# 08_-_Resolver.net
KiCad netlist of a schematic drawn in Altium Designer
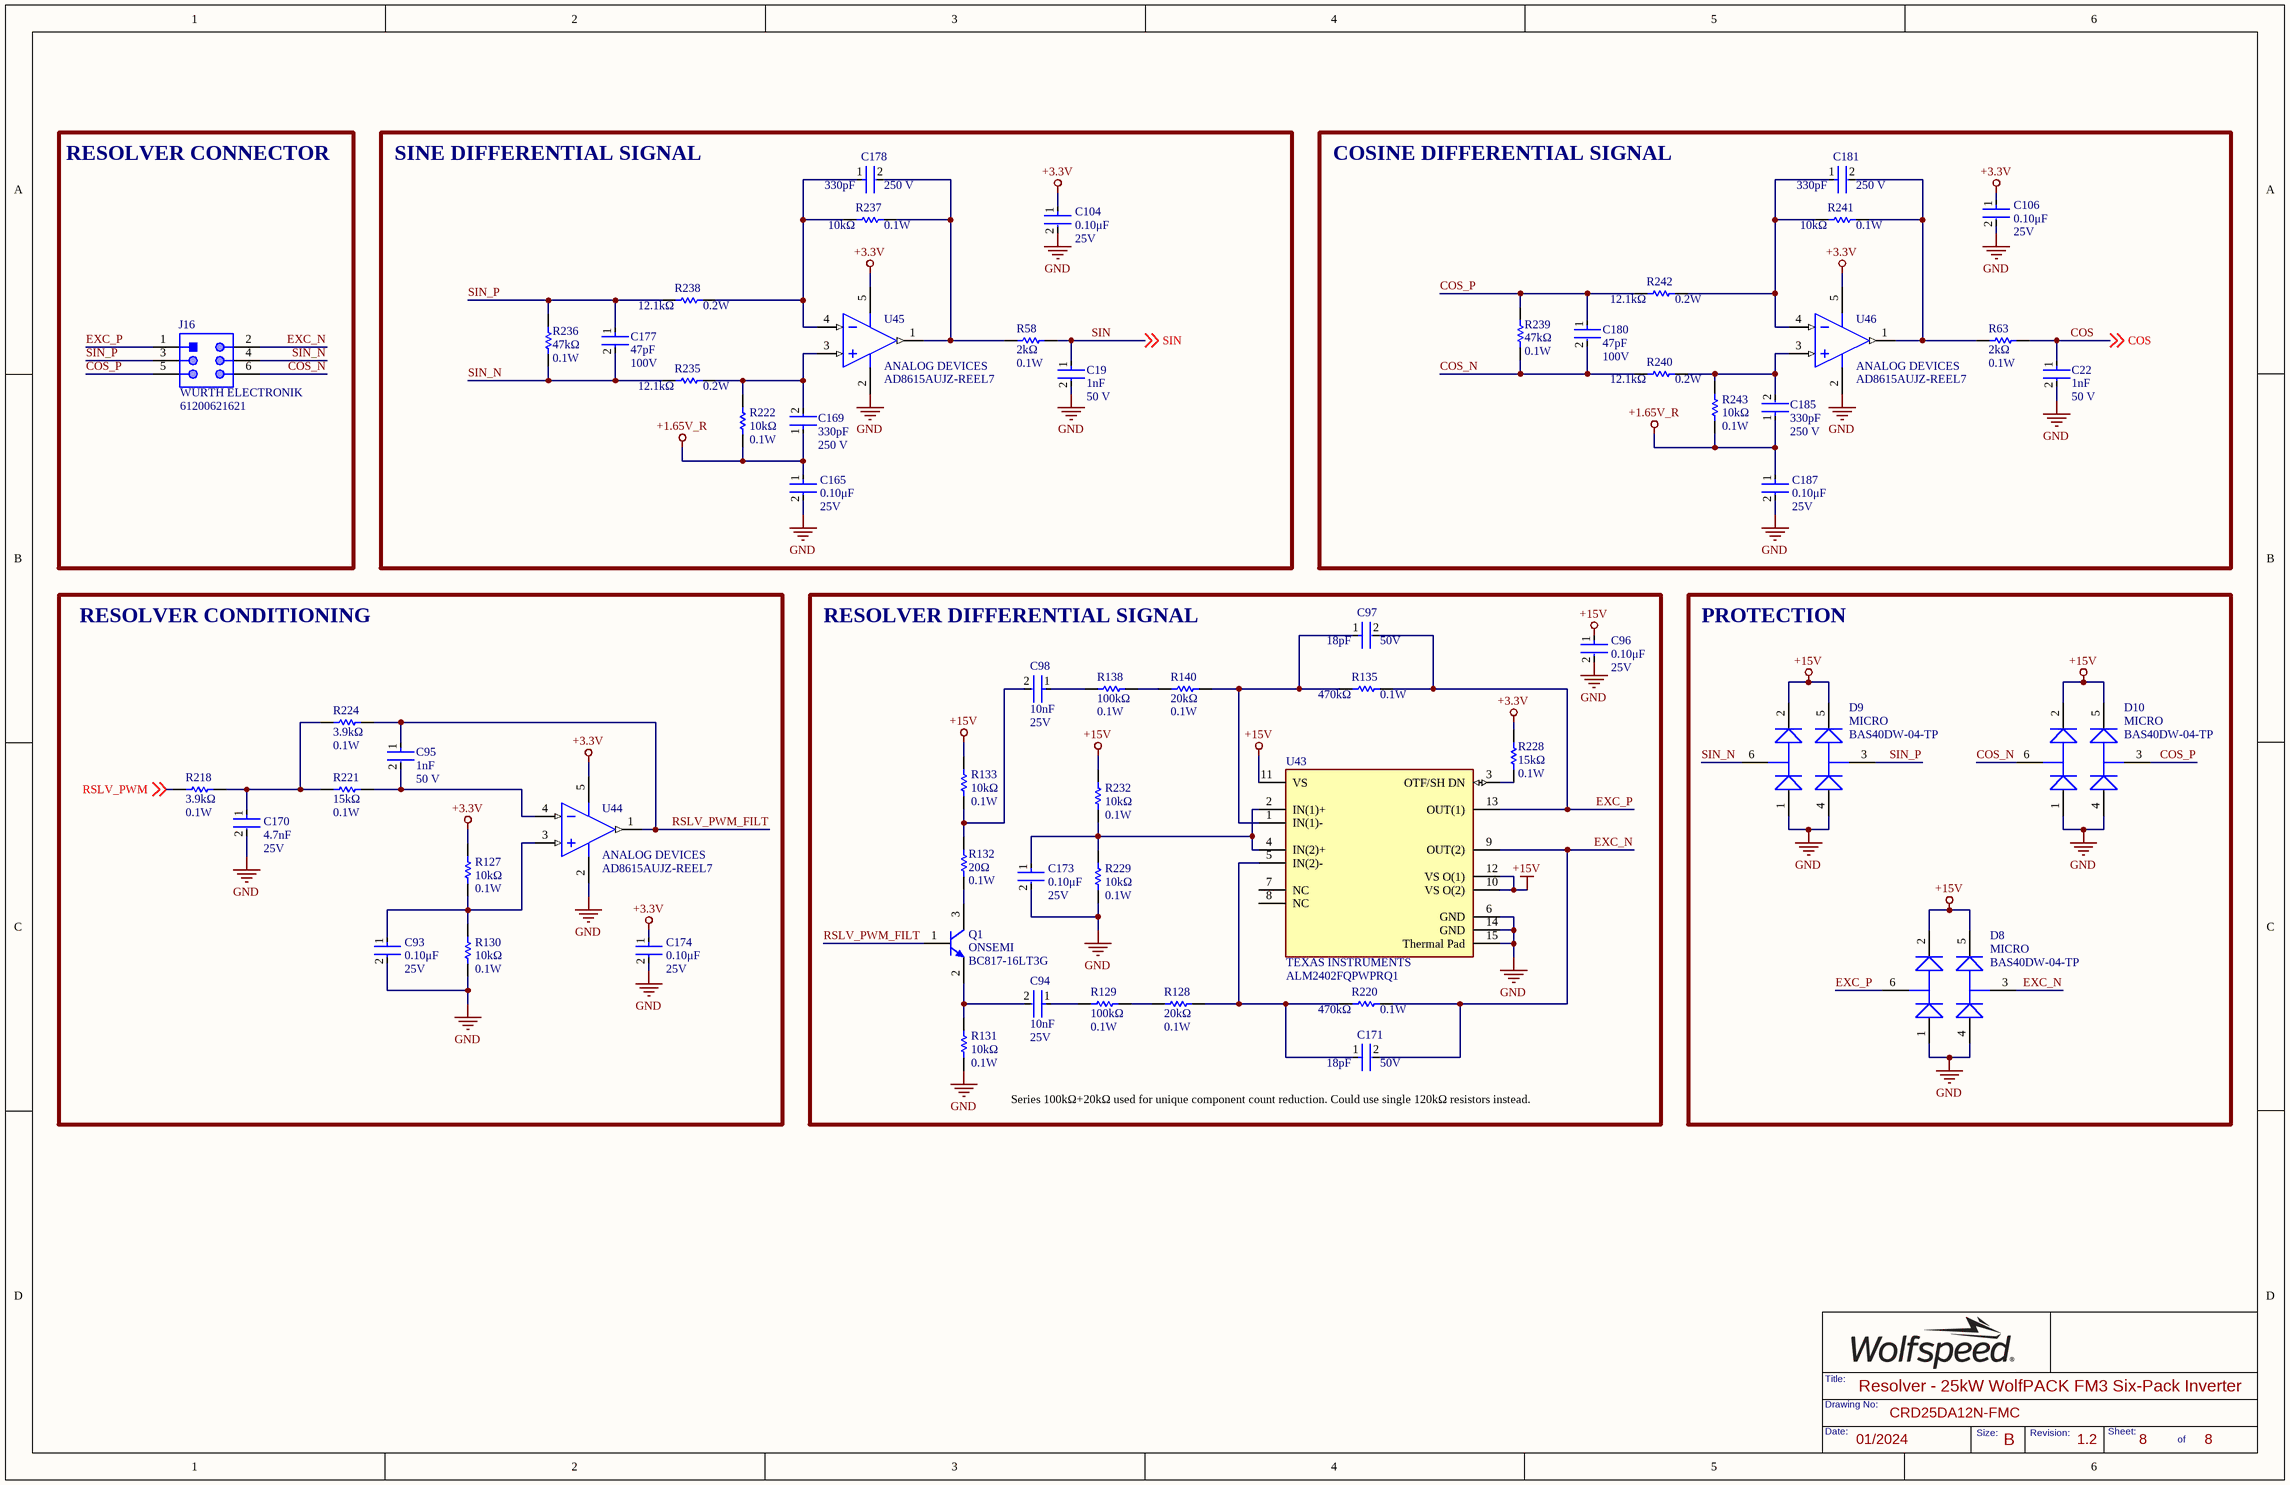
[diagram p0: 08 - Resolver.SchDoc]

(export (version "E")
  (design (tool "Eeschema 10.0.6"))
  (components
    (comp (ref "C19")
      (value "C0603C102K5RACAUTO")
      (footprint "FP-C0603C-CF-IPC_B")
      (description "CAP CER 1000PF 50V X7R 0603")
      (fields
        (field (name "CAPACITANCE") "1nF")
        (field (name "TOLERANCE") "0.1")
        (field (name "VOLTAGE RATING") "50 V")
        (field (name "OCTOPART") "https://octopart.com/c0603c102k5racauto-kemet-18822673")
      )
      (libsource (lib "Altium Content Vault") (part "b4654b650e69147ec39a6b967a45e02"))
    )
    (comp (ref "C22")
      (value "C0603C102K5RACAUTO")
      (footprint "FP-C0603C-CF-IPC_B")
      (description "CAP CER 1000PF 50V X7R 0603")
      (fields
        (field (name "CAPACITANCE") "1nF")
        (field (name "TOLERANCE") "0.1")
        (field (name "VOLTAGE RATING") "50 V")
        (field (name "OCTOPART") "https://octopart.com/c0603c102k5racauto-kemet-18822673")
      )
      (libsource (lib "Altium Content Vault") (part "b4654b650e69147ec39a6b967a45e02"))
    )
    (comp (ref "C93")
      (value "C0603C104K3RACTU")
      (footprint "FP-C0603C-CF-IPC_B")
      (description "CAP CER 0.1UF 25V X7R 0603")
      (fields
        (field (name "VOLTAGE RATING") "25V")
        (field (name "OCTOPART") "https://octopart.com/c0603c104k3ractu-kemet-127541")
        (field (name "MANUFACTURER") "KEMET")
        (field (name "CAPACITANCE") "0.10μF")
      )
      (libsource (lib "Altium Content Vault") (part "b4654b650e69147ec39a6b967a45e02"))
    )
    (comp (ref "C94")
      (value "10nF")
      (footprint "FP-C0603C-CF-IPC_B")
      (description "CAP CER 10000PF 25V X7R 0603")
      (fields
        (field (name "MANUFACTURER") "SAMSUNG")
        (field (name "MANUFACTURER PART NUMBER") "CL10B103KA8WPNC")
        (field (name "VOLTAGE RATING") "25V")
      )
      (libsource (lib "Inverter_25kW") (part "CL10B103KA8WPNC"))
    )
    (comp (ref "C95")
      (value "C0603C102K5RACAUTO")
      (footprint "FP-C0603C-CF-IPC_B")
      (description "CAP CER 1000PF 50V X7R 0603")
      (fields
        (field (name "CAPACITANCE") "1nF")
        (field (name "TOLERANCE") "0.1")
        (field (name "VOLTAGE RATING") "50 V")
        (field (name "OCTOPART") "https://octopart.com/c0603c102k5racauto-kemet-18822673")
      )
      (libsource (lib "Altium Content Vault") (part "b4654b650e69147ec39a6b967a45e02"))
    )
    (comp (ref "C96")
      (value "C0603C104K3RACTU")
      (footprint "FP-C0603C-CF-IPC_B")
      (description "CAP CER 0.1UF 25V X7R 0603")
      (fields
        (field (name "VOLTAGE RATING") "25V")
        (field (name "OCTOPART") "https://octopart.com/c0603c104k3ractu-kemet-127541")
        (field (name "MANUFACTURER") "KEMET")
        (field (name "CAPACITANCE") "0.10μF")
      )
      (libsource (lib "Altium Content Vault") (part "b4654b650e69147ec39a6b967a45e02"))
    )
    (comp (ref "C97")
      (value "06035A180JAT2A")
      (footprint "FP-C0603C-CF-IPC_B")
      (description "CAP CER 18PF 50V C0G/NP0 0603")
      (fields
        (field (name "MANUFACTURER") "KYOCERA AVX")
        (field (name "TOLERANCE") "5%")
        (field (name "CAPACITANCE") "18pF")
        (field (name "VOLTAGE RATING") "50V")
      )
      (libsource (lib "Inverter_25kW") (part "06035A180JAT2A"))
    )
    (comp (ref "C98")
      (value "10nF")
      (footprint "FP-C0603C-CF-IPC_B")
      (description "CAP CER 10000PF 25V X7R 0603")
      (fields
        (field (name "MANUFACTURER") "SAMSUNG")
        (field (name "MANUFACTURER PART NUMBER") "CL10B103KA8WPNC")
        (field (name "VOLTAGE RATING") "25V")
      )
      (libsource (lib "Inverter_25kW") (part "CL10B103KA8WPNC"))
    )
    (comp (ref "C104")
      (value "C0603C104K3RACTU")
      (footprint "FP-C0603C-CF-IPC_B")
      (description "CAP CER 0.1UF 25V X7R 0603")
      (fields
        (field (name "VOLTAGE RATING") "25V")
        (field (name "OCTOPART") "https://octopart.com/c0603c104k3ractu-kemet-127541")
        (field (name "MANUFACTURER") "KEMET")
        (field (name "CAPACITANCE") "0.10μF")
      )
      (libsource (lib "Altium Content Vault") (part "b4654b650e69147ec39a6b967a45e02"))
    )
    (comp (ref "C106")
      (value "C0603C104K3RACTU")
      (footprint "FP-C0603C-CF-IPC_B")
      (description "CAP CER 0.1UF 25V X7R 0603")
      (fields
        (field (name "VOLTAGE RATING") "25V")
        (field (name "OCTOPART") "https://octopart.com/c0603c104k3ractu-kemet-127541")
        (field (name "MANUFACTURER") "KEMET")
        (field (name "CAPACITANCE") "0.10μF")
      )
      (libsource (lib "Altium Content Vault") (part "b4654b650e69147ec39a6b967a45e02"))
    )
    (comp (ref "C165")
      (value "C0603C104K3RACTU")
      (footprint "FP-C0603C-CF-IPC_B")
      (description "CAP CER 0.1UF 25V X7R 0603")
      (fields
        (field (name "VOLTAGE RATING") "25V")
        (field (name "OCTOPART") "https://octopart.com/c0603c104k3ractu-kemet-127541")
        (field (name "MANUFACTURER") "KEMET")
        (field (name "CAPACITANCE") "0.10μF")
      )
      (libsource (lib "Altium Content Vault") (part "b4654b650e69147ec39a6b967a45e02"))
    )
    (comp (ref "C169")
      (value "330pF")
      (footprint "FP-C0603C-CF-IPC_B")
      (description "CAP CER 330PF 250V C0G/NP0 0603")
      (fields
        (field (name "OCTOPART") "https://octopart.com/c0603c331jagac7867-kemet-83501965")
        (field (name "MANUFACTURER PART NUMBER") "C0603C331JAGAC7867")
        (field (name "VOLTAGE RATING") "250 V")
      )
      (libsource (lib "Altium Content Vault") (part "b4654b650e69147ec39a6b967a45e02"))
    )
    (comp (ref "C170")
      (value "C0603C472K3RAC7867")
      (footprint "FP-C0603C-CF-IPC_B")
      (description "CAP CER 4700PF 25V 10% X7R 0603")
      (fields
        (field (name "MANUFACTURER") "KEMET")
        (field (name "MANUFACTURER PART NUMBER") "C0603C472K3RACTU")
        (field (name "VOLTAGE RATING") "25V")
        (field (name "CAPACITANCE") "4.7nF")
      )
      (libsource (lib "Inverter_25kW") (part "C0603C472K3RAC7867"))
    )
    (comp (ref "C171")
      (value "06035A180JAT2A")
      (footprint "FP-C0603C-CF-IPC_B")
      (description "CAP CER 18PF 50V C0G/NP0 0603")
      (fields
        (field (name "MANUFACTURER") "KYOCERA AVX")
        (field (name "TOLERANCE") "5%")
        (field (name "CAPACITANCE") "18pF")
        (field (name "VOLTAGE RATING") "50V")
      )
      (libsource (lib "Inverter_25kW") (part "06035A180JAT2A"))
    )
    (comp (ref "C173")
      (value "C0603C104K3RACTU")
      (footprint "FP-C0603C-CF-IPC_B")
      (description "CAP CER 0.1UF 25V X7R 0603")
      (fields
        (field (name "VOLTAGE RATING") "25V")
        (field (name "OCTOPART") "https://octopart.com/c0603c104k3ractu-kemet-127541")
        (field (name "MANUFACTURER") "KEMET")
        (field (name "CAPACITANCE") "0.10μF")
      )
      (libsource (lib "Altium Content Vault") (part "b4654b650e69147ec39a6b967a45e02"))
    )
    (comp (ref "C174")
      (value "C0603C104K3RACTU")
      (footprint "FP-C0603C-CF-IPC_B")
      (description "CAP CER 0.1UF 25V X7R 0603")
      (fields
        (field (name "VOLTAGE RATING") "25V")
        (field (name "OCTOPART") "https://octopart.com/c0603c104k3ractu-kemet-127541")
        (field (name "MANUFACTURER") "KEMET")
        (field (name "CAPACITANCE") "0.10μF")
      )
      (libsource (lib "Altium Content Vault") (part "b4654b650e69147ec39a6b967a45e02"))
    )
    (comp (ref "C177")
      (value "C0603C470J1GACTU")
      (footprint "FP-C0603C-CF-IPC_B")
      (description "CAP CER 47PF 100V C0G/NP0 0603")
      (fields
        (field (name "MANUFACTURER") "KEMET")
        (field (name "TOLERANCE") "5%")
        (field (name "CAPACITANCE") "47pF")
        (field (name "VOLTAGE RATING (DC)") "100V")
      )
      (libsource (lib "Inverter_25kW") (part "C0603C470J1GACTU"))
    )
    (comp (ref "C178")
      (value "330pF")
      (footprint "FP-C0603C-CF-IPC_B")
      (description "CAP CER 330PF 250V C0G/NP0 0603")
      (fields
        (field (name "OCTOPART") "https://octopart.com/c0603c331jagac7867-kemet-83501965")
        (field (name "MANUFACTURER PART NUMBER") "C0603C331JAGAC7867")
        (field (name "VOLTAGE RATING") "250 V")
      )
      (libsource (lib "Altium Content Vault") (part "b4654b650e69147ec39a6b967a45e02"))
    )
    (comp (ref "C180")
      (value "C0603C470J1GACTU")
      (footprint "FP-C0603C-CF-IPC_B")
      (description "CAP CER 47PF 100V C0G/NP0 0603")
      (fields
        (field (name "MANUFACTURER") "KEMET")
        (field (name "TOLERANCE") "5%")
        (field (name "CAPACITANCE") "47pF")
        (field (name "VOLTAGE RATING (DC)") "100V")
      )
      (libsource (lib "Inverter_25kW") (part "C0603C470J1GACTU"))
    )
    (comp (ref "C181")
      (value "330pF")
      (footprint "FP-C0603C-CF-IPC_B")
      (description "CAP CER 330PF 250V C0G/NP0 0603")
      (fields
        (field (name "OCTOPART") "https://octopart.com/c0603c331jagac7867-kemet-83501965")
        (field (name "MANUFACTURER PART NUMBER") "C0603C331JAGAC7867")
        (field (name "VOLTAGE RATING") "250 V")
      )
      (libsource (lib "Altium Content Vault") (part "b4654b650e69147ec39a6b967a45e02"))
    )
    (comp (ref "C185")
      (value "330pF")
      (footprint "FP-C0603C-CF-IPC_B")
      (description "CAP CER 330PF 250V C0G/NP0 0603")
      (fields
        (field (name "OCTOPART") "https://octopart.com/c0603c331jagac7867-kemet-83501965")
        (field (name "MANUFACTURER PART NUMBER") "C0603C331JAGAC7867")
        (field (name "VOLTAGE RATING") "250 V")
      )
      (libsource (lib "Altium Content Vault") (part "b4654b650e69147ec39a6b967a45e02"))
    )
    (comp (ref "C187")
      (value "C0603C104K3RACTU")
      (footprint "FP-C0603C-CF-IPC_B")
      (description "CAP CER 0.1UF 25V X7R 0603")
      (fields
        (field (name "VOLTAGE RATING") "25V")
        (field (name "OCTOPART") "https://octopart.com/c0603c104k3ractu-kemet-127541")
        (field (name "MANUFACTURER") "KEMET")
        (field (name "CAPACITANCE") "0.10μF")
      )
      (libsource (lib "Altium Content Vault") (part "b4654b650e69147ec39a6b967a45e02"))
    )
    (comp (ref "D8")
      (value "BAS40DW-04-TP")
      (footprint "SOT65P222X120-6N")
      (description "DIODE ARRAY SCHOTTKY 40V SOT363")
      (fields
        (field (name "MANUFACTURER") "MICRO COMMERCIAL")
        (field (name "MANUFACTURER PRINT") "MICRO")
        (field (name "MANUFACTURER PART NUMBER") "BAS40DW-04-TP")
      )
      (libsource (lib "Inverter_25kW") (part "BAS40DW-04-TP"))
    )
    (comp (ref "D9")
      (value "BAS40DW-04-TP")
      (footprint "SOT65P222X120-6N")
      (description "DIODE ARRAY SCHOTTKY 40V SOT363")
      (fields
        (field (name "MANUFACTURER") "MICRO COMMERCIAL")
        (field (name "MANUFACTURER PRINT") "MICRO")
        (field (name "MANUFACTURER PART NUMBER") "BAS40DW-04-TP")
      )
      (libsource (lib "Inverter_25kW") (part "BAS40DW-04-TP"))
    )
    (comp (ref "D10")
      (value "BAS40DW-04-TP")
      (footprint "SOT65P222X120-6N")
      (description "DIODE ARRAY SCHOTTKY 40V SOT363")
      (fields
        (field (name "MANUFACTURER") "MICRO COMMERCIAL")
        (field (name "MANUFACTURER PRINT") "MICRO")
        (field (name "MANUFACTURER PART NUMBER") "BAS40DW-04-TP")
      )
      (libsource (lib "Inverter_25kW") (part "BAS40DW-04-TP"))
    )
    (comp (ref "J16")
      (value "61200621621")
      (footprint "61200621621")
      (description "CONN HEADER VERT 6POS 2.54MM")
      (fields
        (field (name "MANUFACTURER PART NUMBER") "61200621621")
        (field (name "MANUFACTURER") "WURTH ELECTRONIK")
        (field (name "PUBLISHER") "WurthElektronik")
      )
      (libsource (lib "Altium Content Vault") (part "WE-CN-2P-M-R6"))
    )
    (comp (ref "Q1")
      (value "BC817-16LT3G")
      (footprint "ONSC-SOT-23-3-318-08_V")
      (description "TRANS NPN 45V 0.5A SOT23-3")
      (fields (field (name "MANUFACTURER") "ONSEMI") (field (name "MANUFACTURER PART NUMBER") "BC817-16LT3G"))
      (libsource (lib "Altium Content Vault") (part "ONSC-NPN-B1E2C3-3"))
    )
    (comp (ref "R58")
      (value "RT0603DRE072KL")
      (footprint "FP-MCR03-IPC_B")
      (description "RES SMD 2K OHM 0.5% 1/10W 0603")
      (fields
        (field (name "MANUFACTURER") "YAGEO")
        (field (name "TOLERANCE") "0.5%")
        (field (name "RESISTANCE") "2kΩ")
        (field (name "POWER RATING") "0.1W")
      )
      (libsource (lib "Inverter_25kW") (part "RT0603DRE072KL"))
    )
    (comp (ref "R63")
      (value "RT0603DRE072KL")
      (footprint "FP-MCR03-IPC_B")
      (description "RES SMD 2K OHM 0.5% 1/10W 0603")
      (fields
        (field (name "MANUFACTURER") "YAGEO")
        (field (name "TOLERANCE") "0.5%")
        (field (name "RESISTANCE") "2kΩ")
        (field (name "POWER RATING") "0.1W")
      )
      (libsource (lib "Inverter_25kW") (part "RT0603DRE072KL"))
    )
    (comp (ref "R127")
      (value "ERJ3EKF1002V")
      (footprint "FP-MCR03-IPC_B")
      (description "RES SMD 10K OHM 1% 1/10W 0603")
      (fields
        (field (name "MANUFACTURER") "PANASONIC")
        (field (name "MANUFACTURER PART NUMBER") "ERJ-3EKF1002V")
        (field (name "RESISTANCE") "10kΩ")
        (field (name "MAX POWER DISSIPATION") "0.1W")
      )
      (libsource (lib "Inverter_25kW") (part "ERJ3EKF1002V"))
    )
    (comp (ref "R128")
      (value "CRCW060320K0FKTA")
      (footprint "FP-MCR03-IPC_B")
      (description "RES SMD 20K OHM 1% 1/10W 0603")
      (fields
        (field (name "MANUFACTURER") "VISHAY DALE")
        (field (name "TOLERANCE") "1%")
        (field (name "RESISTANCE") "20kΩ")
        (field (name "POWER RATING") "0.1W")
      )
      (libsource (lib "Inverter_25kW") (part "CRCW060320K0FKTA"))
    )
    (comp (ref "R129")
      (value "RC0603FR-07100KL")
      (footprint "FP-MCR03-IPC_B")
      (description "RES 100K OHM 1% 1/10W 0603")
      (fields
        (field (name "MANUFACTURER") "YAGEO")
        (field (name "TOLERANCE") "1%")
        (field (name "RESISTANCE") "100kΩ")
        (field (name "POWER RATING") "0.1W")
      )
      (libsource (lib "Inverter_25kW") (part "RC0603FR-07100KL"))
    )
    (comp (ref "R130")
      (value "ERJ3EKF1002V")
      (footprint "FP-MCR03-IPC_B")
      (description "RES SMD 10K OHM 1% 1/10W 0603")
      (fields
        (field (name "MANUFACTURER") "PANASONIC")
        (field (name "MANUFACTURER PART NUMBER") "ERJ-3EKF1002V")
        (field (name "RESISTANCE") "10kΩ")
        (field (name "MAX POWER DISSIPATION") "0.1W")
      )
      (libsource (lib "Inverter_25kW") (part "ERJ3EKF1002V"))
    )
    (comp (ref "R131")
      (value "ERJ3EKF1002V")
      (footprint "FP-MCR03-IPC_B")
      (description "RES SMD 10K OHM 1% 1/10W 0603")
      (fields
        (field (name "MANUFACTURER") "PANASONIC")
        (field (name "MANUFACTURER PART NUMBER") "ERJ-3EKF1002V")
        (field (name "RESISTANCE") "10kΩ")
        (field (name "MAX POWER DISSIPATION") "0.1W")
      )
      (libsource (lib "Inverter_25kW") (part "ERJ3EKF1002V"))
    )
    (comp (ref "R132")
      (value "RC0603JR-0720RL")
      (footprint "FP-MCR03-IPC_B")
      (description "RES 20 OHM 5% 1/10W 0603")
      (fields
        (field (name "MANUFACTURER") "YAGEO")
        (field (name "TOLERANCE") "5%")
        (field (name "RESISTANCE") "20Ω")
        (field (name "POWER RATING") "0.1W")
      )
      (libsource (lib "Inverter_25kW") (part "RC0603JR-0720RL"))
    )
    (comp (ref "R133")
      (value "ERJ3EKF1002V")
      (footprint "FP-MCR03-IPC_B")
      (description "RES SMD 10K OHM 1% 1/10W 0603")
      (fields
        (field (name "MANUFACTURER") "PANASONIC")
        (field (name "MANUFACTURER PART NUMBER") "ERJ-3EKF1002V")
        (field (name "RESISTANCE") "10kΩ")
        (field (name "MAX POWER DISSIPATION") "0.1W")
      )
      (libsource (lib "Inverter_25kW") (part "ERJ3EKF1002V"))
    )
    (comp (ref "R135")
      (value "RC0603FR-07470KL")
      (footprint "FP-MCR03-IPC_B")
      (description "RES 470K OHM 1% 1/10W 0603")
      (fields
        (field (name "MANUFACTURER") "YAGEO")
        (field (name "TOLERANCE") "1%")
        (field (name "RESISTANCE") "470kΩ")
        (field (name "POWER RATING") "0.1W")
      )
      (libsource (lib "Inverter_25kW") (part "RC0603FR-07470KL"))
    )
    (comp (ref "R138")
      (value "RC0603FR-07100KL")
      (footprint "FP-MCR03-IPC_B")
      (description "RES 100K OHM 1% 1/10W 0603")
      (fields
        (field (name "MANUFACTURER") "YAGEO")
        (field (name "TOLERANCE") "1%")
        (field (name "RESISTANCE") "100kΩ")
        (field (name "POWER RATING") "0.1W")
      )
      (libsource (lib "Inverter_25kW") (part "RC0603FR-07100KL"))
    )
    (comp (ref "R140")
      (value "CRCW060320K0FKTA")
      (footprint "FP-MCR03-IPC_B")
      (description "RES SMD 20K OHM 1% 1/10W 0603")
      (fields
        (field (name "MANUFACTURER") "VISHAY DALE")
        (field (name "TOLERANCE") "1%")
        (field (name "RESISTANCE") "20kΩ")
        (field (name "POWER RATING") "0.1W")
      )
      (libsource (lib "Inverter_25kW") (part "CRCW060320K0FKTA"))
    )
    (comp (ref "R218")
      (value "ERJ3EKF3901V")
      (footprint "FP-MCR03-IPC_B")
      (description "RES SMD 3.9K OHM 1% 1/10W 0603")
      (fields
        (field (name "MANUFACTURER") "PANASONIC")
        (field (name "MANUFACTURER PART NUMBER") "ERJ-3EKF3901V")
        (field (name "RESISTANCE") "3.9kΩ")
        (field (name "POWER RATING") "0.1W")
      )
      (libsource (lib "Inverter_25kW") (part "ERJ3EKF3901V"))
    )
    (comp (ref "R220")
      (value "RC0603FR-07470KL")
      (footprint "FP-MCR03-IPC_B")
      (description "RES 470K OHM 1% 1/10W 0603")
      (fields
        (field (name "MANUFACTURER") "YAGEO")
        (field (name "TOLERANCE") "1%")
        (field (name "RESISTANCE") "470kΩ")
        (field (name "POWER RATING") "0.1W")
      )
      (libsource (lib "Inverter_25kW") (part "RC0603FR-07470KL"))
    )
    (comp (ref "R221")
      (value "ERA-3AED153V")
      (footprint "FP-MCR03-IPC_B")
      (description "RES SMD 15K OHM 0.5% 1/10W 0603")
      (fields
        (field (name "MANUFACTURER") "PANASONIC")
        (field (name "TOLERANCE") "0.5%")
        (field (name "RESISTANCE") "15kΩ")
        (field (name "POWER RATING") "0.1W")
      )
      (libsource (lib "Inverter_25kW") (part "ERA-3AED153V"))
    )
    (comp (ref "R222")
      (value "ERJ3EKF1002V")
      (footprint "FP-MCR03-IPC_B")
      (description "RES SMD 10K OHM 1% 1/10W 0603")
      (fields
        (field (name "MANUFACTURER") "PANASONIC")
        (field (name "MANUFACTURER PART NUMBER") "ERJ-3EKF1002V")
        (field (name "RESISTANCE") "10kΩ")
        (field (name "MAX POWER DISSIPATION") "0.1W")
      )
      (libsource (lib "Inverter_25kW") (part "ERJ3EKF1002V"))
    )
    (comp (ref "R224")
      (value "ERJ3EKF3901V")
      (footprint "FP-MCR03-IPC_B")
      (description "RES SMD 3.9K OHM 1% 1/10W 0603")
      (fields
        (field (name "MANUFACTURER") "PANASONIC")
        (field (name "MANUFACTURER PART NUMBER") "ERJ-3EKF3901V")
        (field (name "RESISTANCE") "3.9kΩ")
        (field (name "POWER RATING") "0.1W")
      )
      (libsource (lib "Inverter_25kW") (part "ERJ3EKF3901V"))
    )
    (comp (ref "R228")
      (value "ERA-3AED153V")
      (footprint "FP-MCR03-IPC_B")
      (description "RES SMD 15K OHM 0.5% 1/10W 0603")
      (fields
        (field (name "MANUFACTURER") "PANASONIC")
        (field (name "TOLERANCE") "0.5%")
        (field (name "RESISTANCE") "15kΩ")
        (field (name "POWER RATING") "0.1W")
      )
      (libsource (lib "Inverter_25kW") (part "ERA-3AED153V"))
    )
    (comp (ref "R229")
      (value "ERJ3EKF1002V")
      (footprint "FP-MCR03-IPC_B")
      (description "RES SMD 10K OHM 1% 1/10W 0603")
      (fields
        (field (name "MANUFACTURER") "PANASONIC")
        (field (name "MANUFACTURER PART NUMBER") "ERJ-3EKF1002V")
        (field (name "RESISTANCE") "10kΩ")
        (field (name "MAX POWER DISSIPATION") "0.1W")
      )
      (libsource (lib "Inverter_25kW") (part "ERJ3EKF1002V"))
    )
    (comp (ref "R232")
      (value "ERJ3EKF1002V")
      (footprint "FP-MCR03-IPC_B")
      (description "RES SMD 10K OHM 1% 1/10W 0603")
      (fields
        (field (name "MANUFACTURER") "PANASONIC")
        (field (name "MANUFACTURER PART NUMBER") "ERJ-3EKF1002V")
        (field (name "RESISTANCE") "10kΩ")
        (field (name "MAX POWER DISSIPATION") "0.1W")
      )
      (libsource (lib "Inverter_25kW") (part "ERJ3EKF1002V"))
    )
    (comp (ref "R235")
      (value "ERJ-PB3B1212V")
      (footprint "FP-MCR03-IPC_B")
      (description "RES SMD 12.1K OHM 0.1% 1/5W 0603")
      (fields
        (field (name "MANUFACTURER") "PANASONIC")
        (field (name "TOLERANCE") "0.1%")
        (field (name "RESISTANCE") "12.1kΩ")
        (field (name "MAX POWER DISSIPATION") "0.2W")
      )
      (libsource (lib "Inverter_25kW") (part "ERJ-PB3B1212V"))
    )
    (comp (ref "R236")
      (value "RC0603FR-0747KL")
      (footprint "FP-MCR03-IPC_B")
      (description "RES 47K OHM 1% 1/10W 0603")
      (fields
        (field (name "MANUFACTURER") "YAGEO")
        (field (name "TOLERANCE") "1%")
        (field (name "RESISTANCE") "47kΩ")
        (field (name "POWER RATING") "0.1W")
      )
      (libsource (lib "Inverter_25kW") (part "RC0603FR-0747KL"))
    )
    (comp (ref "R237")
      (value "ERJ3EKF1002V")
      (footprint "FP-MCR03-IPC_B")
      (description "RES SMD 10K OHM 1% 1/10W 0603")
      (fields
        (field (name "MANUFACTURER") "PANASONIC")
        (field (name "MANUFACTURER PART NUMBER") "ERJ-3EKF1002V")
        (field (name "RESISTANCE") "10kΩ")
        (field (name "MAX POWER DISSIPATION") "0.1W")
      )
      (libsource (lib "Inverter_25kW") (part "ERJ3EKF1002V"))
    )
    (comp (ref "R238")
      (value "ERJ-PB3B1212V")
      (footprint "FP-MCR03-IPC_B")
      (description "RES SMD 12.1K OHM 0.1% 1/5W 0603")
      (fields
        (field (name "MANUFACTURER") "PANASONIC")
        (field (name "TOLERANCE") "0.1%")
        (field (name "RESISTANCE") "12.1kΩ")
        (field (name "MAX POWER DISSIPATION") "0.2W")
      )
      (libsource (lib "Inverter_25kW") (part "ERJ-PB3B1212V"))
    )
    (comp (ref "R239")
      (value "RC0603FR-0747KL")
      (footprint "FP-MCR03-IPC_B")
      (description "RES 47K OHM 1% 1/10W 0603")
      (fields
        (field (name "MANUFACTURER") "YAGEO")
        (field (name "TOLERANCE") "1%")
        (field (name "RESISTANCE") "47kΩ")
        (field (name "POWER RATING") "0.1W")
      )
      (libsource (lib "Inverter_25kW") (part "RC0603FR-0747KL"))
    )
    (comp (ref "R240")
      (value "ERJ-PB3B1212V")
      (footprint "FP-MCR03-IPC_B")
      (description "RES SMD 12.1K OHM 0.1% 1/5W 0603")
      (fields
        (field (name "MANUFACTURER") "PANASONIC")
        (field (name "TOLERANCE") "0.1%")
        (field (name "RESISTANCE") "12.1kΩ")
        (field (name "MAX POWER DISSIPATION") "0.2W")
      )
      (libsource (lib "Inverter_25kW") (part "ERJ-PB3B1212V"))
    )
    (comp (ref "R241")
      (value "ERJ3EKF1002V")
      (footprint "FP-MCR03-IPC_B")
      (description "RES SMD 10K OHM 1% 1/10W 0603")
      (fields
        (field (name "MANUFACTURER") "PANASONIC")
        (field (name "MANUFACTURER PART NUMBER") "ERJ-3EKF1002V")
        (field (name "RESISTANCE") "10kΩ")
        (field (name "MAX POWER DISSIPATION") "0.1W")
      )
      (libsource (lib "Inverter_25kW") (part "ERJ3EKF1002V"))
    )
    (comp (ref "R242")
      (value "ERJ-PB3B1212V")
      (footprint "FP-MCR03-IPC_B")
      (description "RES SMD 12.1K OHM 0.1% 1/5W 0603")
      (fields
        (field (name "MANUFACTURER") "PANASONIC")
        (field (name "TOLERANCE") "0.1%")
        (field (name "RESISTANCE") "12.1kΩ")
        (field (name "MAX POWER DISSIPATION") "0.2W")
      )
      (libsource (lib "Inverter_25kW") (part "ERJ-PB3B1212V"))
    )
    (comp (ref "R243")
      (value "ERJ3EKF1002V")
      (footprint "FP-MCR03-IPC_B")
      (description "RES SMD 10K OHM 1% 1/10W 0603")
      (fields
        (field (name "MANUFACTURER") "PANASONIC")
        (field (name "MANUFACTURER PART NUMBER") "ERJ-3EKF1002V")
        (field (name "RESISTANCE") "10kΩ")
        (field (name "MAX POWER DISSIPATION") "0.1W")
      )
      (libsource (lib "Inverter_25kW") (part "ERJ3EKF1002V"))
    )
    (comp (ref "U43")
      (value "ALM2402FQPWPRQ1")
      (footprint "FP-PWP0014H-MFG")
      (description "IC POWER 2 CIRCUIT 14HTSSOP")
      (fields
        (field (name "MANUFACTURER PART NUMBER") "ALM2402FQPWPRQ1")
        (field (name "MANUFACTURER") "TEXAS INSTRUMENTS")
      )
      (libsource (lib "CRD25DA12N-FMC") (part "CMP-04895-000282-1"))
    )
    (comp (ref "U44")
      (value "AD8615AUJZ-REEL7")
      (footprint "ADI-UJ-5_M")
      (description "IC OPAMP GP 1 CIRCUIT TSOT23-5")
      (fields
        (field (name "MANUFACTURER") "ANALOG DEVICES")
        (field (name "GENERIC PART NUMBER") "AD8615")
        (field (name "MANUFACTURER PART NUMBER") "AD8615AUJZ-REEL7")
      )
      (libsource (lib "Altium Content Vault") (part "ADI-ADxxxx-X-5"))
    )
    (comp (ref "U45")
      (value "AD8615AUJZ-REEL7")
      (footprint "ADI-UJ-5_M")
      (description "IC OPAMP GP 1 CIRCUIT TSOT23-5")
      (fields
        (field (name "MANUFACTURER") "ANALOG DEVICES")
        (field (name "GENERIC PART NUMBER") "AD8615")
        (field (name "MANUFACTURER PART NUMBER") "AD8615AUJZ-REEL7")
      )
      (libsource (lib "Altium Content Vault") (part "ADI-ADxxxx-X-5"))
    )
    (comp (ref "U46")
      (value "AD8615AUJZ-REEL7")
      (footprint "ADI-UJ-5_M")
      (description "IC OPAMP GP 1 CIRCUIT TSOT23-5")
      (fields
        (field (name "MANUFACTURER") "ANALOG DEVICES")
        (field (name "GENERIC PART NUMBER") "AD8615")
        (field (name "MANUFACTURER PART NUMBER") "AD8615AUJZ-REEL7")
      )
      (libsource (lib "Altium Content Vault") (part "ADI-ADxxxx-X-5"))
    )
  )
  (nets
    (net (code "1") (name "+1.65V_R") (class "Default")
      (node (ref "C165") (pin "1") (pinfunction "1_1") (pintype "passive"))
      (node (ref "C169") (pin "1") (pinfunction "1_1") (pintype "passive"))
      (node (ref "C185") (pin "1") (pinfunction "1_1") (pintype "passive"))
      (node (ref "C187") (pin "1") (pinfunction "1_1") (pintype "passive"))
      (node (ref "R222") (pin "1") (pinfunction "1_1") (pintype "passive"))
      (node (ref "R243") (pin "1") (pinfunction "1_1") (pintype "passive"))
    )
    (net (code "2") (name "+3.3V") (class "Default")
      (node (ref "C104") (pin "1") (pinfunction "1_1") (pintype "passive"))
      (node (ref "C106") (pin "1") (pinfunction "1_1") (pintype "passive"))
      (node (ref "C174") (pin "1") (pinfunction "1_1") (pintype "passive"))
      (node (ref "R127") (pin "2") (pinfunction "2_2") (pintype "passive"))
      (node (ref "R228") (pin "2") (pinfunction "2_2") (pintype "passive"))
      (node (ref "U44") (pin "5") (pinfunction "+V_5") (pintype "power_in"))
      (node (ref "U45") (pin "5") (pinfunction "+V_5") (pintype "power_in"))
      (node (ref "U46") (pin "5") (pinfunction "+V_5") (pintype "power_in"))
    )
    (net (code "3") (name "+15V") (class "Default")
      (node (ref "C96") (pin "1") (pinfunction "1_1") (pintype "passive"))
      (node (ref "D10") (pin "2") (pinfunction "C1_2") (pintype "passive"))
      (node (ref "D10") (pin "5") (pinfunction "C2_5") (pintype "passive"))
      (node (ref "D8") (pin "2") (pinfunction "C1_2") (pintype "passive"))
      (node (ref "D8") (pin "5") (pinfunction "C2_5") (pintype "passive"))
      (node (ref "D9") (pin "2") (pinfunction "C1_2") (pintype "passive"))
      (node (ref "D9") (pin "5") (pinfunction "C2_5") (pintype "passive"))
      (node (ref "R133") (pin "2") (pinfunction "2_2") (pintype "passive"))
      (node (ref "R232") (pin "2") (pinfunction "2_2") (pintype "passive"))
      (node (ref "U43") (pin "10") (pinfunction "VS_O(2)_10") (pintype "power_in"))
      (node (ref "U43") (pin "11") (pinfunction "VS_11") (pintype "power_in"))
      (node (ref "U43") (pin "12") (pinfunction "VS_O(1)_12") (pintype "power_in"))
    )
    (net (code "4") (name "/COS_N") (class "Default")
      (node (ref "C180") (pin "2") (pinfunction "2_2") (pintype "passive"))
      (node (ref "D10") (pin "6") (pinfunction "AC1_6") (pintype "passive"))
      (node (ref "J16") (pin "6") (pinfunction "6_6") (pintype "passive"))
      (node (ref "R239") (pin "1") (pinfunction "1_1") (pintype "passive"))
      (node (ref "R240") (pin "1") (pinfunction "1_1") (pintype "passive"))
    )
    (net (code "5") (name "/COS_P") (class "Default")
      (node (ref "C180") (pin "1") (pinfunction "1_1") (pintype "passive"))
      (node (ref "D10") (pin "3") (pinfunction "AC2_3") (pintype "passive"))
      (node (ref "J16") (pin "5") (pinfunction "5_5") (pintype "passive"))
      (node (ref "R239") (pin "2") (pinfunction "2_2") (pintype "passive"))
      (node (ref "R242") (pin "1") (pinfunction "1_1") (pintype "passive"))
    )
    (net (code "6") (name "/EXC_N") (class "Default")
      (node (ref "C171") (pin "2") (pinfunction "2_2") (pintype "passive"))
      (node (ref "D8") (pin "3") (pinfunction "AC2_3") (pintype "passive"))
      (node (ref "J16") (pin "2") (pinfunction "2_2") (pintype "passive"))
      (node (ref "R220") (pin "2") (pinfunction "2_2") (pintype "passive"))
      (node (ref "U43") (pin "9") (pinfunction "OUT(2)_9") (pintype "passive"))
    )
    (net (code "7") (name "/EXC_P") (class "Default")
      (node (ref "C97") (pin "2") (pinfunction "2_2") (pintype "passive"))
      (node (ref "D8") (pin "6") (pinfunction "AC1_6") (pintype "passive"))
      (node (ref "J16") (pin "1") (pinfunction "1_1") (pintype "passive"))
      (node (ref "R135") (pin "2") (pinfunction "2_2") (pintype "passive"))
      (node (ref "U43") (pin "13") (pinfunction "OUT(1)_13") (pintype "passive"))
    )
    (net (code "8") (name "/RSLV_PWM_FILT") (class "Default")
      (node (ref "C95") (pin "1") (pinfunction "1_1") (pintype "passive"))
      (node (ref "Q1") (pin "1") (pinfunction "B_1") (pintype "passive"))
      (node (ref "R224") (pin "2") (pinfunction "2_2") (pintype "passive"))
      (node (ref "U44") (pin "1") (pinfunction "OUT_1") (pintype "output"))
    )
    (net (code "9") (name "/SIN_N") (class "Default")
      (node (ref "C177") (pin "2") (pinfunction "2_2") (pintype "passive"))
      (node (ref "D9") (pin "6") (pinfunction "AC1_6") (pintype "passive"))
      (node (ref "J16") (pin "4") (pinfunction "4_4") (pintype "passive"))
      (node (ref "R235") (pin "1") (pinfunction "1_1") (pintype "passive"))
      (node (ref "R236") (pin "1") (pinfunction "1_1") (pintype "passive"))
    )
    (net (code "10") (name "/SIN_P") (class "Default")
      (node (ref "C177") (pin "1") (pinfunction "1_1") (pintype "passive"))
      (node (ref "D9") (pin "3") (pinfunction "AC2_3") (pintype "passive"))
      (node (ref "J16") (pin "3") (pinfunction "3_3") (pintype "passive"))
      (node (ref "R236") (pin "2") (pinfunction "2_2") (pintype "passive"))
      (node (ref "R238") (pin "1") (pinfunction "1_1") (pintype "passive"))
    )
    (net (code "11") (name "COS") (class "Default")
      (node (ref "C22") (pin "1") (pinfunction "1_1") (pintype "passive"))
      (node (ref "R63") (pin "2") (pinfunction "2_2") (pintype "passive"))
    )
    (net (code "12") (name "GND") (class "Default")
      (node (ref "C104") (pin "2") (pinfunction "2_2") (pintype "passive"))
      (node (ref "C106") (pin "2") (pinfunction "2_2") (pintype "passive"))
      (node (ref "C165") (pin "2") (pinfunction "2_2") (pintype "passive"))
      (node (ref "C170") (pin "2") (pinfunction "2_2") (pintype "passive"))
      (node (ref "C173") (pin "2") (pinfunction "2_2") (pintype "passive"))
      (node (ref "C174") (pin "2") (pinfunction "2_2") (pintype "passive"))
      (node (ref "C187") (pin "2") (pinfunction "2_2") (pintype "passive"))
      (node (ref "C19") (pin "2") (pinfunction "2_2") (pintype "passive"))
      (node (ref "C22") (pin "2") (pinfunction "2_2") (pintype "passive"))
      (node (ref "C93") (pin "2") (pinfunction "2_2") (pintype "passive"))
      (node (ref "C96") (pin "2") (pinfunction "2_2") (pintype "passive"))
      (node (ref "D10") (pin "1") (pinfunction "A1_1") (pintype "passive"))
      (node (ref "D10") (pin "4") (pinfunction "A2_4") (pintype "passive"))
      (node (ref "D8") (pin "1") (pinfunction "A1_1") (pintype "passive"))
      (node (ref "D8") (pin "4") (pinfunction "A2_4") (pintype "passive"))
      (node (ref "D9") (pin "1") (pinfunction "A1_1") (pintype "passive"))
      (node (ref "D9") (pin "4") (pinfunction "A2_4") (pintype "passive"))
      (node (ref "R130") (pin "1") (pinfunction "1_1") (pintype "passive"))
      (node (ref "R131") (pin "1") (pinfunction "1_1") (pintype "passive"))
      (node (ref "R229") (pin "1") (pinfunction "1_1") (pintype "passive"))
      (node (ref "U43") (pin "14") (pinfunction "GND_14") (pintype "power_in"))
      (node (ref "U43") (pin "15") (pinfunction "Thermal_Pad_15") (pintype "power_in"))
      (node (ref "U43") (pin "6") (pinfunction "GND_6") (pintype "power_in"))
      (node (ref "U44") (pin "2") (pinfunction "-V_2") (pintype "power_in"))
      (node (ref "U45") (pin "2") (pinfunction "-V_2") (pintype "power_in"))
      (node (ref "U46") (pin "2") (pinfunction "-V_2") (pintype "power_in"))
    )
    (net (code "13") (name "Net-(C94-Pad1)") (class "Default")
      (node (ref "C94") (pin "1") (pinfunction "1_1") (pintype "passive"))
      (node (ref "R129") (pin "2") (pinfunction "2_2") (pintype "passive"))
    )
    (net (code "14") (name "Net-(C98-Pad1)") (class "Default")
      (node (ref "C98") (pin "1") (pinfunction "1_1") (pintype "passive"))
      (node (ref "R138") (pin "2") (pinfunction "2_2") (pintype "passive"))
    )
    (net (code "15") (name "Net-(C98-Pad2)") (class "Default")
      (node (ref "C98") (pin "2") (pinfunction "2_2") (pintype "passive"))
      (node (ref "R132") (pin "2") (pinfunction "2_2") (pintype "passive"))
      (node (ref "R133") (pin "1") (pinfunction "1_1") (pintype "passive"))
    )
    (net (code "16") (name "Net-(C170-Pad1)") (class "Default")
      (node (ref "C170") (pin "1") (pinfunction "1_1") (pintype "passive"))
      (node (ref "R218") (pin "2") (pinfunction "2_2") (pintype "passive"))
      (node (ref "R221") (pin "2") (pinfunction "2_2") (pintype "passive"))
      (node (ref "R224") (pin "1") (pinfunction "1_1") (pintype "passive"))
    )
    (net (code "17") (name "Net-(Q1-C)") (class "Default")
      (node (ref "Q1") (pin "3") (pinfunction "C_3") (pintype "passive"))
      (node (ref "R132") (pin "1") (pinfunction "1_1") (pintype "passive"))
    )
    (net (code "18") (name "Net-(Q1-E)") (class "Default")
      (node (ref "C94") (pin "2") (pinfunction "2_2") (pintype "passive"))
      (node (ref "Q1") (pin "2") (pinfunction "E_2") (pintype "passive"))
      (node (ref "R131") (pin "2") (pinfunction "2_2") (pintype "passive"))
    )
    (net (code "19") (name "Net-(R128-Pad2)") (class "Default")
      (node (ref "R128") (pin "2") (pinfunction "2_2") (pintype "passive"))
      (node (ref "R129") (pin "1") (pinfunction "1_1") (pintype "passive"))
    )
    (net (code "20") (name "Net-(R138-Pad1)") (class "Default")
      (node (ref "R138") (pin "1") (pinfunction "1_1") (pintype "passive"))
      (node (ref "R140") (pin "2") (pinfunction "2_2") (pintype "passive"))
    )
    (net (code "21") (name "Net-(U43-IN(1)+)") (class "Default")
      (node (ref "C173") (pin "1") (pinfunction "1_1") (pintype "passive"))
      (node (ref "R229") (pin "2") (pinfunction "2_2") (pintype "passive"))
      (node (ref "R232") (pin "1") (pinfunction "1_1") (pintype "passive"))
      (node (ref "U43") (pin "2") (pinfunction "IN(1)+_2") (pintype "tri_state"))
      (node (ref "U43") (pin "4") (pinfunction "IN(2)+_4") (pintype "tri_state"))
    )
    (net (code "22") (name "Net-(U43-IN(1)-)") (class "Default")
      (node (ref "C97") (pin "1") (pinfunction "1_1") (pintype "passive"))
      (node (ref "R135") (pin "1") (pinfunction "1_1") (pintype "passive"))
      (node (ref "R140") (pin "1") (pinfunction "1_1") (pintype "passive"))
      (node (ref "U43") (pin "1") (pinfunction "IN(1)-_1") (pintype "tri_state"))
    )
    (net (code "23") (name "Net-(U43-IN(2)-)") (class "Default")
      (node (ref "C171") (pin "1") (pinfunction "1_1") (pintype "passive"))
      (node (ref "R128") (pin "1") (pinfunction "1_1") (pintype "passive"))
      (node (ref "R220") (pin "1") (pinfunction "1_1") (pintype "passive"))
      (node (ref "U43") (pin "5") (pinfunction "IN(2)-_5") (pintype "tri_state"))
    )
    (net (code "24") (name "Net-(U43-OTF{slash}SH_DN)") (class "Default")
      (node (ref "R228") (pin "1") (pinfunction "1_1") (pintype "passive"))
      (node (ref "U43") (pin "3") (pinfunction "OTF/SH_DN_3") (pintype "bidirectional"))
    )
    (net (code "25") (name "Net-(U44-+IN)") (class "Default")
      (node (ref "C93") (pin "1") (pinfunction "1_1") (pintype "passive"))
      (node (ref "R127") (pin "1") (pinfunction "1_1") (pintype "passive"))
      (node (ref "R130") (pin "2") (pinfunction "2_2") (pintype "passive"))
      (node (ref "U44") (pin "3") (pinfunction "+IN_3") (pintype "input"))
    )
    (net (code "26") (name "Net-(U44--IN)") (class "Default")
      (node (ref "C95") (pin "2") (pinfunction "2_2") (pintype "passive"))
      (node (ref "R221") (pin "1") (pinfunction "1_1") (pintype "passive"))
      (node (ref "U44") (pin "4") (pinfunction "-IN_4") (pintype "input"))
    )
    (net (code "27") (name "Net-(U45-+IN)") (class "Default")
      (node (ref "C169") (pin "2") (pinfunction "2_2") (pintype "passive"))
      (node (ref "R222") (pin "2") (pinfunction "2_2") (pintype "passive"))
      (node (ref "R235") (pin "2") (pinfunction "2_2") (pintype "passive"))
      (node (ref "U45") (pin "3") (pinfunction "+IN_3") (pintype "input"))
    )
    (net (code "28") (name "Net-(U45--IN)") (class "Default")
      (node (ref "C178") (pin "1") (pinfunction "1_1") (pintype "passive"))
      (node (ref "R237") (pin "2") (pinfunction "2_2") (pintype "passive"))
      (node (ref "R238") (pin "2") (pinfunction "2_2") (pintype "passive"))
      (node (ref "U45") (pin "4") (pinfunction "-IN_4") (pintype "input"))
    )
    (net (code "29") (name "Net-(U45-OUT)") (class "Default")
      (node (ref "C178") (pin "2") (pinfunction "2_2") (pintype "passive"))
      (node (ref "R237") (pin "1") (pinfunction "1_1") (pintype "passive"))
      (node (ref "R58") (pin "1") (pinfunction "1_1") (pintype "passive"))
      (node (ref "U45") (pin "1") (pinfunction "OUT_1") (pintype "output"))
    )
    (net (code "30") (name "Net-(U46-+IN)") (class "Default")
      (node (ref "C185") (pin "2") (pinfunction "2_2") (pintype "passive"))
      (node (ref "R240") (pin "2") (pinfunction "2_2") (pintype "passive"))
      (node (ref "R243") (pin "2") (pinfunction "2_2") (pintype "passive"))
      (node (ref "U46") (pin "3") (pinfunction "+IN_3") (pintype "input"))
    )
    (net (code "31") (name "Net-(U46--IN)") (class "Default")
      (node (ref "C181") (pin "1") (pinfunction "1_1") (pintype "passive"))
      (node (ref "R241") (pin "2") (pinfunction "2_2") (pintype "passive"))
      (node (ref "R242") (pin "2") (pinfunction "2_2") (pintype "passive"))
      (node (ref "U46") (pin "4") (pinfunction "-IN_4") (pintype "input"))
    )
    (net (code "32") (name "Net-(U46-OUT)") (class "Default")
      (node (ref "C181") (pin "2") (pinfunction "2_2") (pintype "passive"))
      (node (ref "R241") (pin "1") (pinfunction "1_1") (pintype "passive"))
      (node (ref "R63") (pin "1") (pinfunction "1_1") (pintype "passive"))
      (node (ref "U46") (pin "1") (pinfunction "OUT_1") (pintype "output"))
    )
    (net (code "33") (name "RSLV_PWM") (class "Default")
      (node (ref "R218") (pin "1") (pinfunction "1_1") (pintype "passive"))
    )
    (net (code "34") (name "SIN") (class "Default")
      (node (ref "C19") (pin "1") (pinfunction "1_1") (pintype "passive"))
      (node (ref "R58") (pin "2") (pinfunction "2_2") (pintype "passive"))
    )
    (net (code "35") (name "unconnected-(U43-NC-Pad7)") (class "Default")
      (node (ref "U43") (pin "7") (pinfunction "NC_7") (pintype "passive"))
    )
    (net (code "36") (name "unconnected-(U43-NC-Pad8)") (class "Default")
      (node (ref "U43") (pin "8") (pinfunction "NC_8") (pintype "passive"))
    )
  )
)
